# sch.net
KiCad netlist of a schematic drawn in EasyEDA
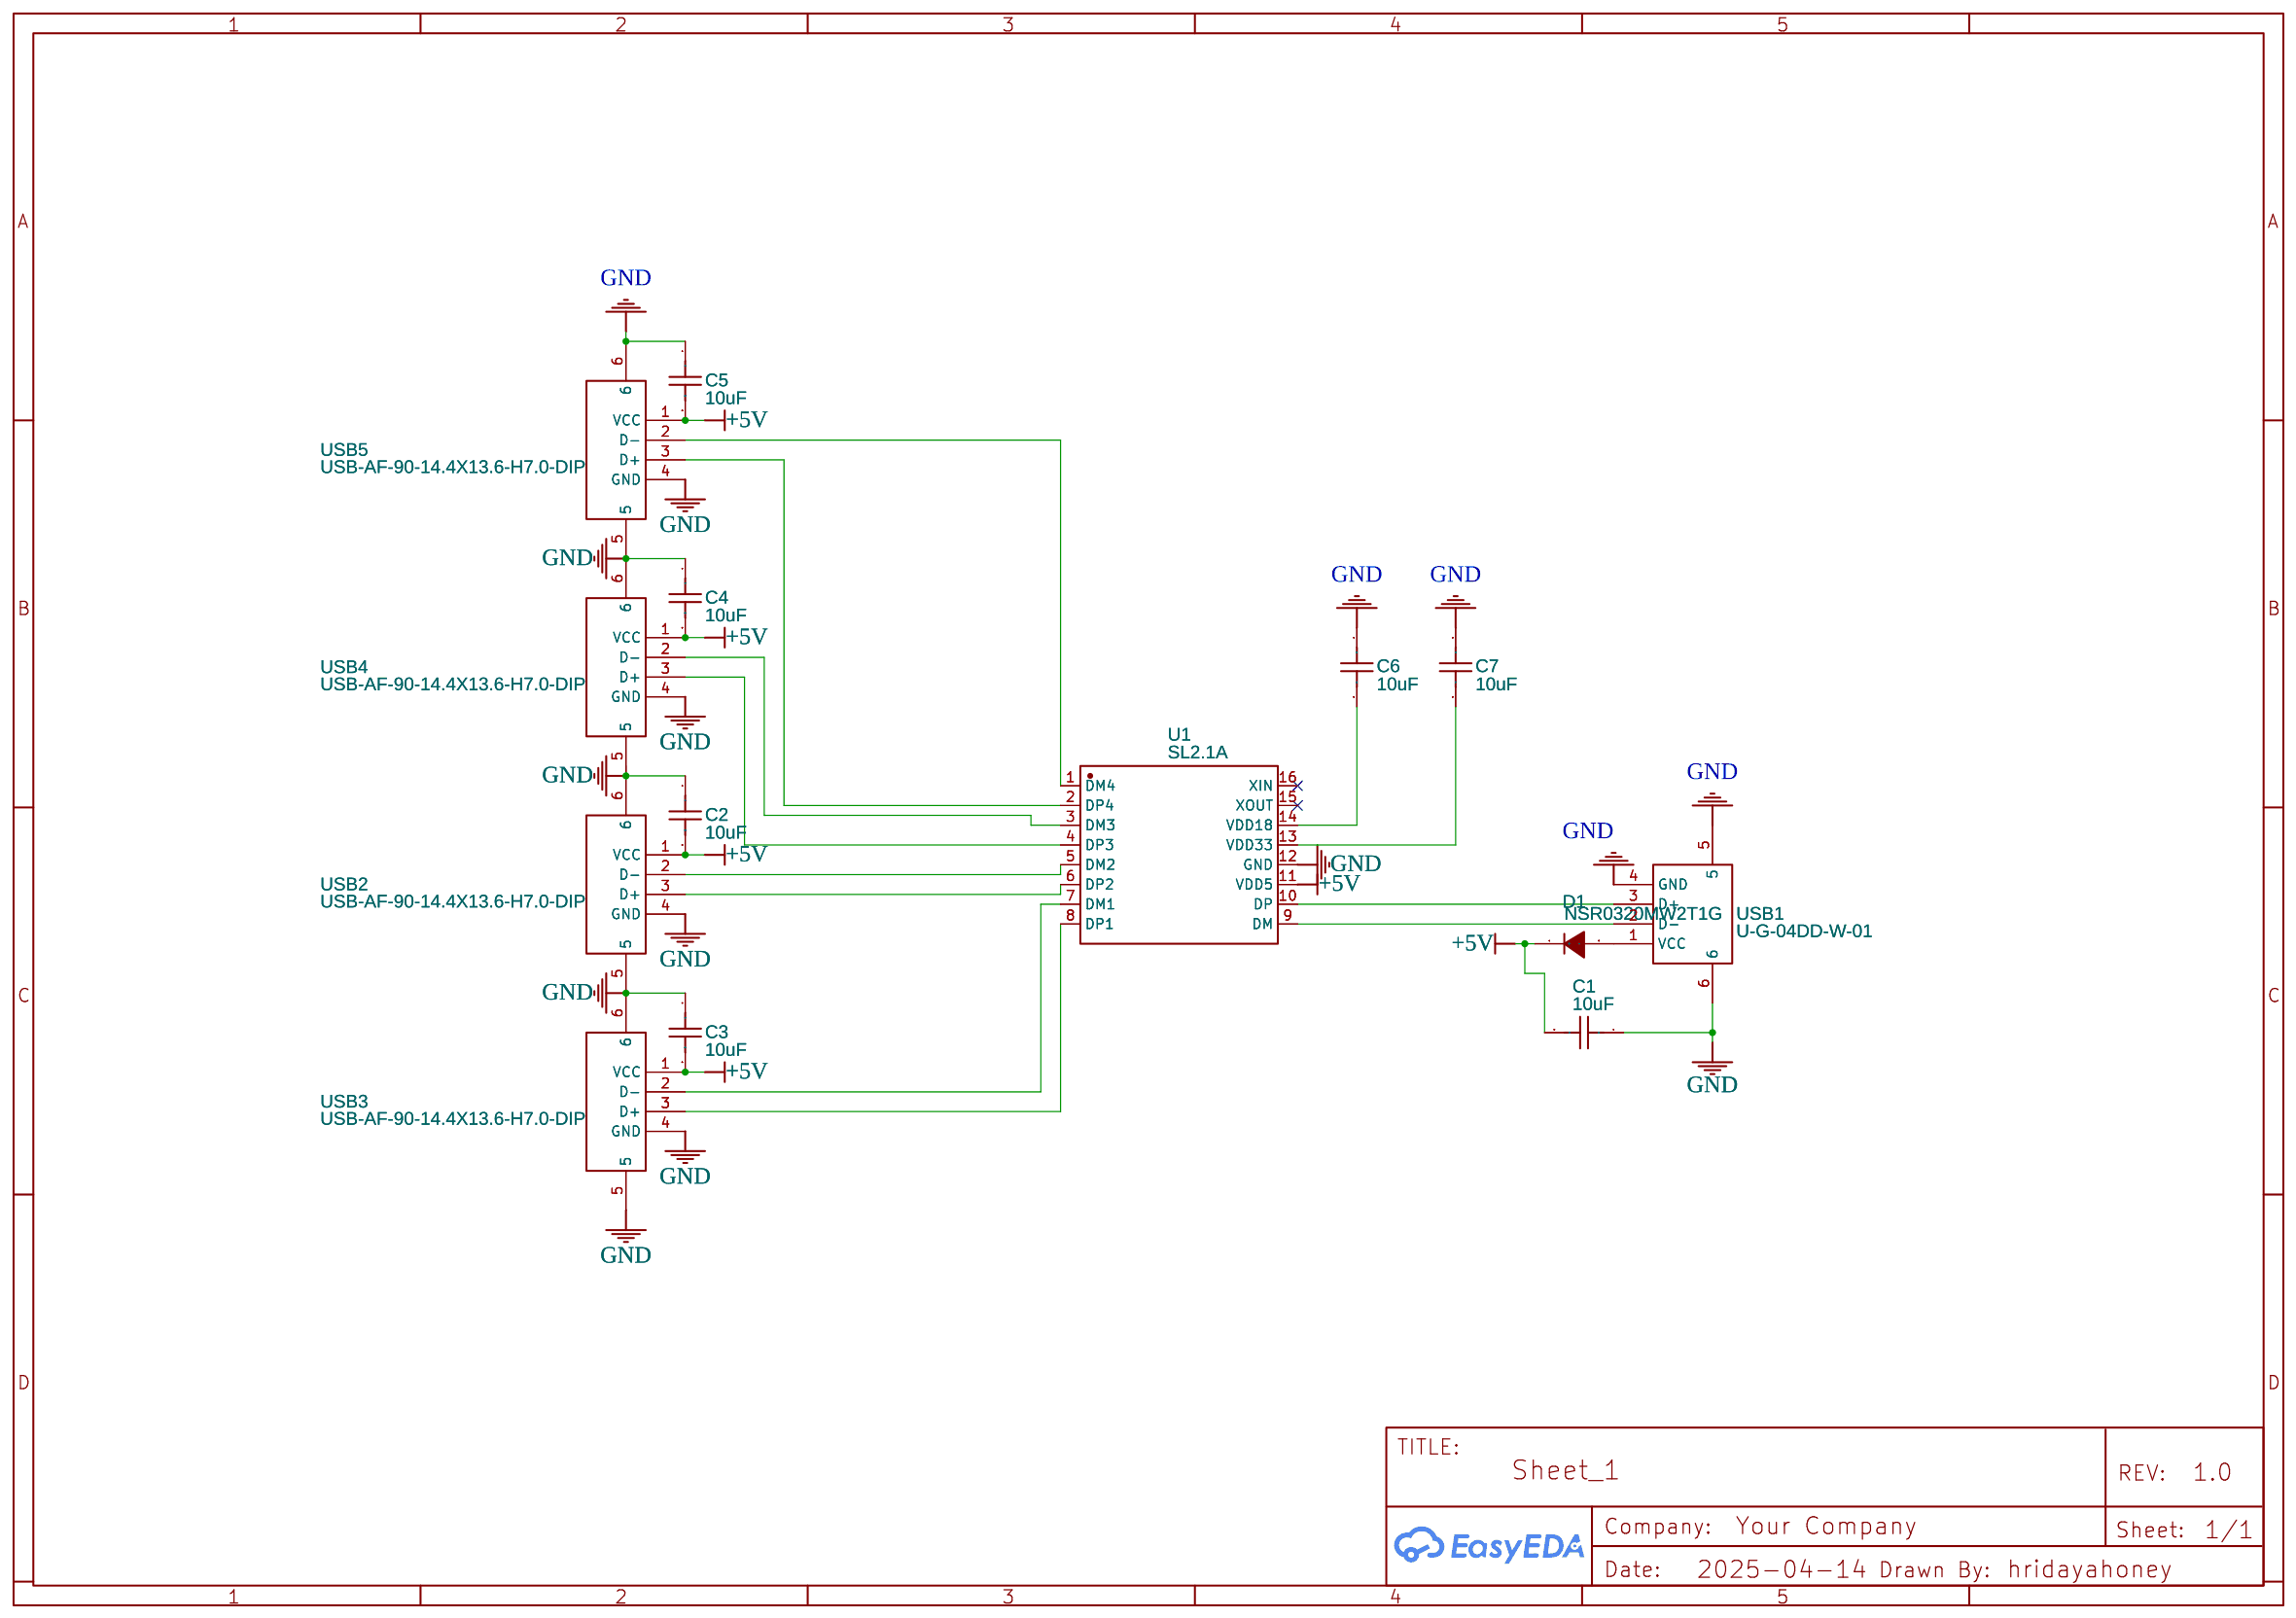
[diagram p0: schematic sheet]

(export (version "E")
  (design (tool "Eeschema 10.0.6"))
  (components
    (comp (ref "C1")
      (value "10uF")
      (fields
        (field (name "Manufacturer Part") "CL10A106KP8NNNC")
        (field (name "Manufacturer") "SAMSUNG(三星)")
      )
      (libsource (lib "") (part "CL10A106KP8NNNC_1"))
    )
    (comp (ref "C2")
      (value "10uF")
      (fields
        (field (name "Manufacturer Part") "CL10A106KP8NNNC")
        (field (name "Manufacturer") "SAMSUNG(三星)")
      )
      (libsource (lib "") (part "CL10A106KP8NNNC"))
    )
    (comp (ref "C3")
      (value "10uF")
      (fields
        (field (name "Manufacturer Part") "CL10A106KP8NNNC")
        (field (name "Manufacturer") "SAMSUNG(三星)")
      )
      (libsource (lib "") (part "CL10A106KP8NNNC"))
    )
    (comp (ref "C4")
      (value "10uF")
      (fields
        (field (name "Manufacturer Part") "CL10A106KP8NNNC")
        (field (name "Manufacturer") "SAMSUNG(三星)")
      )
      (libsource (lib "") (part "CL10A106KP8NNNC"))
    )
    (comp (ref "C5")
      (value "10uF")
      (fields
        (field (name "Manufacturer Part") "CL10A106KP8NNNC")
        (field (name "Manufacturer") "SAMSUNG(三星)")
      )
      (libsource (lib "") (part "CL10A106KP8NNNC"))
    )
    (comp (ref "C6")
      (value "10uF")
      (fields
        (field (name "Manufacturer Part") "CL10A106KP8NNNC")
        (field (name "Manufacturer") "SAMSUNG(三星)")
      )
      (libsource (lib "") (part "CL10A106KP8NNNC"))
    )
    (comp (ref "C7")
      (value "10uF")
      (fields
        (field (name "Manufacturer Part") "CL10A106KP8NNNC")
        (field (name "Manufacturer") "SAMSUNG(三星)")
      )
      (libsource (lib "") (part "CL10A106KP8NNNC"))
    )
    (comp (ref "D1")
      (value "NSR0320MW2T1G")
      (fields (field (name "Manufacturer") "onsemi(安森美)"))
      (libsource (lib "") (part "NSR0320MW2T1G"))
    )
    (comp (ref "U1")
      (value "SL2.1A")
      (fields (field (name "Manufacturer") "CoreChips(和芯润德)"))
      (libsource (lib "") (part "SL2.1A"))
    )
    (comp (ref "USB1")
      (value "U-G-04DD-W-01")
      (fields (field (name "Manufacturer Part") "U-G-O4DD-W-1") (field (name "Manufacturer") "韩国韩荣"))
      (libsource (lib "") (part "U-G-04DD-W-01"))
    )
    (comp (ref "USB2")
      (value "USB-AF-90-14.4X13.6-H7.0-DIP")
      (fields (field (name "Manufacturer Part") "903-131A1011D10100") (field (name "Manufacturer") "精拓金"))
      (libsource (lib "") (part "USB-AF-90-14.4X13.6-H7.0-DIP"))
    )
    (comp (ref "USB3")
      (value "USB-AF-90-14.4X13.6-H7.0-DIP")
      (fields (field (name "Manufacturer Part") "903-131A1011D10100") (field (name "Manufacturer") "精拓金"))
      (libsource (lib "") (part "USB-AF-90-14.4X13.6-H7.0-DIP"))
    )
    (comp (ref "USB4")
      (value "USB-AF-90-14.4X13.6-H7.0-DIP")
      (fields (field (name "Manufacturer Part") "903-131A1011D10100") (field (name "Manufacturer") "精拓金"))
      (libsource (lib "") (part "USB-AF-90-14.4X13.6-H7.0-DIP"))
    )
    (comp (ref "USB5")
      (value "USB-AF-90-14.4X13.6-H7.0-DIP")
      (fields (field (name "Manufacturer Part") "903-131A1011D10100") (field (name "Manufacturer") "精拓金"))
      (libsource (lib "") (part "USB-AF-90-14.4X13.6-H7.0-DIP"))
    )
  )
  (nets
    (net (code "1") (name "+5V") (class "Default")
      (node (ref "C1") (pin "2") (pinfunction "2_2") (pintype "unspecified"))
      (node (ref "C2") (pin "2") (pinfunction "2_2") (pintype "unspecified"))
      (node (ref "C3") (pin "2") (pinfunction "2_2") (pintype "unspecified"))
      (node (ref "C4") (pin "2") (pinfunction "2_2") (pintype "unspecified"))
      (node (ref "C5") (pin "2") (pinfunction "2_2") (pintype "unspecified"))
      (node (ref "D1") (pin "1") (pinfunction "C_1") (pintype "unspecified"))
      (node (ref "U1") (pin "11") (pinfunction "VDD5_11") (pintype "unspecified"))
      (node (ref "USB2") (pin "1") (pinfunction "VCC_1") (pintype "unspecified"))
      (node (ref "USB3") (pin "1") (pinfunction "VCC_1") (pintype "unspecified"))
      (node (ref "USB4") (pin "1") (pinfunction "VCC_1") (pintype "unspecified"))
      (node (ref "USB5") (pin "1") (pinfunction "VCC_1") (pintype "unspecified"))
    )
    (net (code "2") (name "GND") (class "Default")
      (node (ref "C1") (pin "1") (pinfunction "1_1") (pintype "unspecified"))
      (node (ref "C2") (pin "1") (pinfunction "1_1") (pintype "unspecified"))
      (node (ref "C3") (pin "1") (pinfunction "1_1") (pintype "unspecified"))
      (node (ref "C4") (pin "1") (pinfunction "1_1") (pintype "unspecified"))
      (node (ref "C5") (pin "1") (pinfunction "1_1") (pintype "unspecified"))
      (node (ref "C6") (pin "1") (pinfunction "1_1") (pintype "unspecified"))
      (node (ref "C7") (pin "1") (pinfunction "1_1") (pintype "unspecified"))
      (node (ref "U1") (pin "12") (pinfunction "GND_12") (pintype "unspecified"))
      (node (ref "USB1") (pin "4") (pinfunction "GND_4") (pintype "unspecified"))
      (node (ref "USB1") (pin "5") (pinfunction "5_5") (pintype "unspecified"))
      (node (ref "USB1") (pin "6") (pinfunction "6_6") (pintype "unspecified"))
      (node (ref "USB2") (pin "4") (pinfunction "GND_4") (pintype "unspecified"))
      (node (ref "USB2") (pin "5") (pinfunction "5_5") (pintype "unspecified"))
      (node (ref "USB2") (pin "6") (pinfunction "6_6") (pintype "unspecified"))
      (node (ref "USB3") (pin "4") (pinfunction "GND_4") (pintype "unspecified"))
      (node (ref "USB3") (pin "5") (pinfunction "5_5") (pintype "unspecified"))
      (node (ref "USB3") (pin "6") (pinfunction "6_6") (pintype "unspecified"))
      (node (ref "USB4") (pin "4") (pinfunction "GND_4") (pintype "unspecified"))
      (node (ref "USB4") (pin "5") (pinfunction "5_5") (pintype "unspecified"))
      (node (ref "USB4") (pin "6") (pinfunction "6_6") (pintype "unspecified"))
      (node (ref "USB5") (pin "4") (pinfunction "GND_4") (pintype "unspecified"))
      (node (ref "USB5") (pin "5") (pinfunction "5_5") (pintype "unspecified"))
      (node (ref "USB5") (pin "6") (pinfunction "6_6") (pintype "unspecified"))
    )
    (net (code "3") (name "Net-(D1-A)") (class "Default")
      (node (ref "D1") (pin "2") (pinfunction "A_2") (pintype "unspecified"))
      (node (ref "USB1") (pin "1") (pinfunction "VCC_1") (pintype "unspecified"))
    )
    (net (code "4") (name "Net-(U1-DM)") (class "Default")
      (node (ref "U1") (pin "9") (pinfunction "DM_9") (pintype "unspecified"))
      (node (ref "USB1") (pin "2") (pinfunction "D-_2") (pintype "unspecified"))
    )
    (net (code "5") (name "Net-(U1-DM1)") (class "Default")
      (node (ref "U1") (pin "7") (pinfunction "DM1_7") (pintype "unspecified"))
      (node (ref "USB3") (pin "2") (pinfunction "D-_2") (pintype "unspecified"))
    )
    (net (code "6") (name "Net-(U1-DM2)") (class "Default")
      (node (ref "U1") (pin "5") (pinfunction "DM2_5") (pintype "unspecified"))
      (node (ref "USB2") (pin "2") (pinfunction "D-_2") (pintype "unspecified"))
    )
    (net (code "7") (name "Net-(U1-DM3)") (class "Default")
      (node (ref "U1") (pin "3") (pinfunction "DM3_3") (pintype "unspecified"))
      (node (ref "USB4") (pin "2") (pinfunction "D-_2") (pintype "unspecified"))
    )
    (net (code "8") (name "Net-(U1-DM4)") (class "Default")
      (node (ref "U1") (pin "1") (pinfunction "DM4_1") (pintype "unspecified"))
      (node (ref "USB5") (pin "2") (pinfunction "D-_2") (pintype "unspecified"))
    )
    (net (code "9") (name "Net-(U1-DP)") (class "Default")
      (node (ref "U1") (pin "10") (pinfunction "DP_10") (pintype "unspecified"))
      (node (ref "USB1") (pin "3") (pinfunction "D+_3") (pintype "unspecified"))
    )
    (net (code "10") (name "Net-(U1-DP1)") (class "Default")
      (node (ref "U1") (pin "8") (pinfunction "DP1_8") (pintype "unspecified"))
      (node (ref "USB3") (pin "3") (pinfunction "D+_3") (pintype "unspecified"))
    )
    (net (code "11") (name "Net-(U1-DP2)") (class "Default")
      (node (ref "U1") (pin "6") (pinfunction "DP2_6") (pintype "unspecified"))
      (node (ref "USB2") (pin "3") (pinfunction "D+_3") (pintype "unspecified"))
    )
    (net (code "12") (name "Net-(U1-DP3)") (class "Default")
      (node (ref "U1") (pin "4") (pinfunction "DP3_4") (pintype "unspecified"))
      (node (ref "USB4") (pin "3") (pinfunction "D+_3") (pintype "unspecified"))
    )
    (net (code "13") (name "Net-(U1-DP4)") (class "Default")
      (node (ref "U1") (pin "2") (pinfunction "DP4_2") (pintype "unspecified"))
      (node (ref "USB5") (pin "3") (pinfunction "D+_3") (pintype "unspecified"))
    )
    (net (code "14") (name "Net-(U1-VDD18)") (class "Default")
      (node (ref "C6") (pin "2") (pinfunction "2_2") (pintype "unspecified"))
      (node (ref "U1") (pin "14") (pinfunction "VDD18_14") (pintype "unspecified"))
    )
    (net (code "15") (name "Net-(U1-VDD33)") (class "Default")
      (node (ref "C7") (pin "2") (pinfunction "2_2") (pintype "unspecified"))
      (node (ref "U1") (pin "13") (pinfunction "VDD33_13") (pintype "unspecified"))
    )
    (net (code "16") (name "unconnected-(U1-XIN-Pad16)") (class "Default")
      (node (ref "U1") (pin "16") (pinfunction "XIN_16") (pintype "unspecified+no_connect"))
    )
    (net (code "17") (name "unconnected-(U1-XOUT-Pad15)") (class "Default")
      (node (ref "U1") (pin "15") (pinfunction "XOUT_15") (pintype "unspecified+no_connect"))
    )
  )
)
